# Channel.net
KiCad netlist of a schematic drawn in Altium Designer
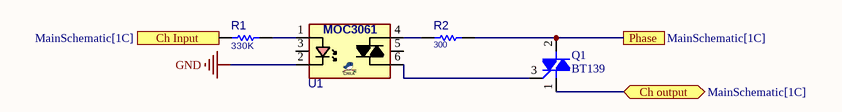
[diagram p0: Channel.SchDoc]

(export (version "E")
  (design (tool "Eeschema 10.0.6"))
  (components
    (comp (ref "Q1")
      (value "BT139")
      (footprint "TO220_3")
      (description "Triac, 600V, 4A, TO-220, Silicon Bidirectional Thyristor")
      (libsource (lib "triac_diac") (part "TRIAC"))
    )
    (comp (ref "R1")
      (value "330K")
      (footprint "R1206")
      (description "RESISTOR, SMD")
      (libsource (lib "passive_smd") (part "RES_SMD"))
    )
    (comp (ref "R2")
      (value "300")
      (footprint "R025W_AX_VER")
      (description "RESISTOR, THD")
      (fields (field (name "MANF_P#") "RK73H1ETTP4701F") (field (name "MANF") "KOA SPEER"))
      (libsource (lib "passive_thd") (part "RES_THD"))
    )
    (comp (ref "U1")
      (value "MOC3061")
      (footprint "DIP_6")
      (description "OPTOTRIAC, 600v/1A, 6v In")
      (libsource (lib "optocoupler") (part "OPT_TRIAC6P_MOC3061"))
    )
  )
  (nets
    (net (code "1") (name "/Ch Input") (class "Default")
      (node (ref "R1") (pin "2") (pinfunction "2_2") (pintype "passive"))
    )
    (net (code "2") (name "/Ch output") (class "Default")
      (node (ref "Q1") (pin "1") (pinfunction "T1_1") (pintype "passive"))
    )
    (net (code "3") (name "/Phase") (class "Default")
      (node (ref "Q1") (pin "2") (pinfunction "T2_2") (pintype "passive"))
      (node (ref "R2") (pin "2") (pinfunction "2_2") (pintype "passive"))
    )
    (net (code "4") (name "GND") (class "Default")
      (node (ref "U1") (pin "2") (pinfunction "K_2") (pintype "passive"))
    )
    (net (code "5") (name "Net-(Q1-G)") (class "Default")
      (node (ref "Q1") (pin "3") (pinfunction "G_3") (pintype "passive"))
      (node (ref "U1") (pin "6") (pinfunction "A/K_6") (pintype "passive"))
    )
    (net (code "6") (name "Net-(R2-Pad1)") (class "Default")
      (node (ref "R2") (pin "1") (pinfunction "1_1") (pintype "passive"))
      (node (ref "U1") (pin "4") (pinfunction "A/K_4") (pintype "passive"))
    )
    (net (code "7") (name "Net-(U1-A)") (class "Default")
      (node (ref "R1") (pin "1") (pinfunction "1_1") (pintype "passive"))
      (node (ref "U1") (pin "1") (pinfunction "A_1") (pintype "passive"))
    )
    (net (code "8") (name "unconnected-(U1-NC-Pad3)") (class "Default")
      (node (ref "U1") (pin "3") (pinfunction "NC_3") (pintype "passive"))
    )
    (net (code "9") (name "unconnected-(U1-NC-Pad5)") (class "Default")
      (node (ref "U1") (pin "5") (pinfunction "NC_5") (pintype "passive"))
    )
  )
)
